# DB4100_DRV_v0_2.net
KiCad netlist of a schematic drawn in Altium Designer
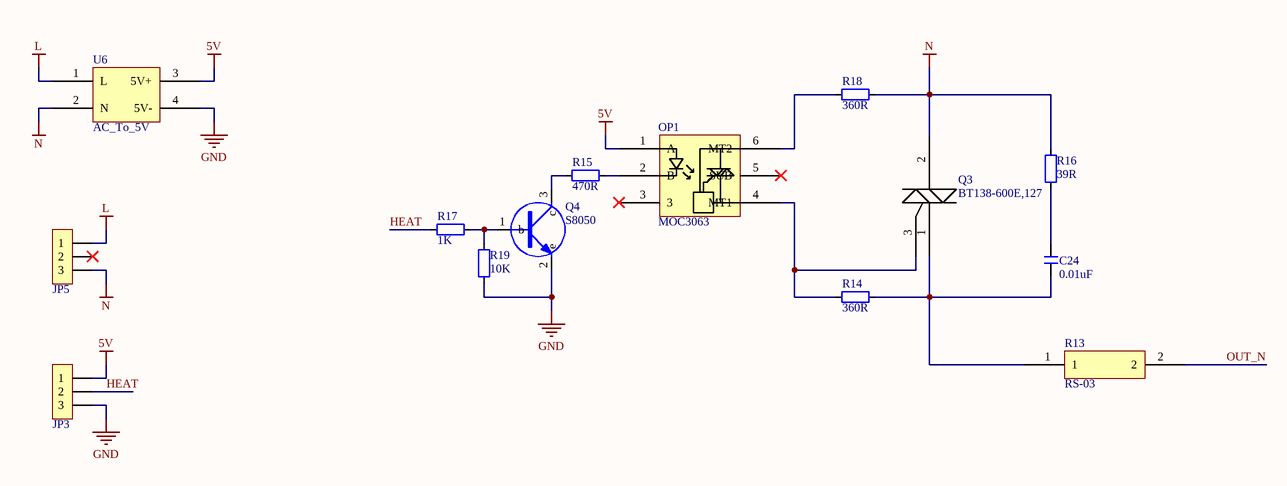
[diagram p0: DB4100_DRV_v0.2.SchDoc]

(export (version "E")
  (design (tool "Eeschema 10.0.6"))
  (components
    (comp (ref "C24")
      (value "0.01uF")
      (footprint "MLCC5.08-A")
      (description "独石电容")
      (fields (field (name "版权归属") "源创客"))
      (libsource (lib "电容") (part "C-MLCC"))
    )
    (comp (ref "JP3")
      (value "HDR-1X3")
      (footprint "XH2.54-3P")
      (description "3P接插件")
      (fields (field (name "版权归属") "源创客"))
      (libsource (lib "排针-排母") (part "Header 3"))
    )
    (comp (ref "JP5")
      (value "HDR-1X3")
      (footprint "VH3.96-3PWB")
      (description "3P接插件")
      (fields (field (name "版权归属") "源创客"))
      (libsource (lib "排针-排母") (part "Header 3"))
    )
    (comp (ref "OP1")
      (value "MOC3063")
      (footprint "MOC3063")
      (description "双向可控硅")
      (libsource (lib "常用芯片") (part "MOC3063"))
    )
    (comp (ref "Q3")
      (value "BT138-600E,127")
      (footprint "BT138-600E,127")
      (description "晶闸管(可控硅)/模块")
      (libsource (lib "二极管-整流桥") (part "BT138-600E,127"))
    )
    (comp (ref "Q4") (value "S8050") (footprint "SOT23-3L") (libsource (lib "三极管") (part "NPN")))
    (comp (ref "R13")
      (value "RS-03")
      (footprint "RS-03")
      (description "电吹风热保护器")
      (libsource (lib "模块器件") (part "RS-03"))
    )
    (comp (ref "R14")
      (value "360R")
      (footprint "R 1206")
      (description "贴片电阻")
      (fields (field (name "版权归属") "源创客"))
      (libsource (lib "") (part "R_1"))
    )
    (comp (ref "R15")
      (value "470R")
      (footprint "R 0603")
      (description "贴片电阻")
      (fields (field (name "版权归属") "源创客"))
      (libsource (lib "电阻") (part "R"))
    )
    (comp (ref "R16")
      (value "39R")
      (footprint "R 1206")
      (description "贴片电阻")
      (fields (field (name "版权归属") "源创客"))
      (libsource (lib "") (part "R_2"))
    )
    (comp (ref "R17")
      (value "1K")
      (footprint "R 0603")
      (description "贴片电阻")
      (fields (field (name "版权归属") "源创客"))
      (libsource (lib "电阻") (part "R"))
    )
    (comp (ref "R18")
      (value "360R")
      (footprint "R 1206")
      (description "贴片电阻")
      (fields (field (name "版权归属") "源创客"))
      (libsource (lib "") (part "R_1"))
    )
    (comp (ref "R19")
      (value "10K")
      (footprint "R 0603")
      (description "贴片电阻")
      (fields (field (name "版权归属") "源创客"))
      (libsource (lib "") (part "R_1"))
    )
    (comp (ref "U6")
      (value "AC_To_5V")
      (footprint "ACTo5v")
      (description "220V转5V降压模块")
      (libsource (lib "变压器") (part "AC_To_5V"))
    )
  )
  (nets
    (net (code "1") (name "/HEAT") (class "Default")
      (node (ref "JP3") (pin "2") (pinfunction "2_2") (pintype "passive"))
      (node (ref "R17") (pin "1") (pinfunction "1_1") (pintype "passive"))
    )
    (net (code "2") (name "/OUT_N") (class "Default")
      (node (ref "R13") (pin "2") (pinfunction "2_2") (pintype "passive"))
    )
    (net (code "3") (name "5V") (class "Default")
      (node (ref "JP3") (pin "1") (pinfunction "1_1") (pintype "passive"))
      (node (ref "OP1") (pin "1") (pinfunction "A_1") (pintype "passive"))
      (node (ref "U6") (pin "3") (pinfunction "5V+_3") (pintype "passive"))
    )
    (net (code "4") (name "GND") (class "Default")
      (node (ref "JP3") (pin "3") (pinfunction "3_3") (pintype "passive"))
      (node (ref "Q4") (pin "2") (pinfunction "e_2") (pintype "passive"))
      (node (ref "R19") (pin "1") (pinfunction "1_1") (pintype "passive"))
      (node (ref "U6") (pin "4") (pinfunction "5V-_4") (pintype "passive"))
    )
    (net (code "5") (name "L") (class "Default")
      (node (ref "JP5") (pin "1") (pinfunction "1_1") (pintype "passive"))
      (node (ref "U6") (pin "1") (pinfunction "L_1") (pintype "passive"))
    )
    (net (code "6") (name "N") (class "Default")
      (node (ref "JP5") (pin "3") (pinfunction "3_3") (pintype "passive"))
      (node (ref "Q3") (pin "2") (pinfunction "2_2") (pintype "passive"))
      (node (ref "R16") (pin "1") (pinfunction "1_1") (pintype "passive"))
      (node (ref "R18") (pin "2") (pinfunction "2_2") (pintype "passive"))
      (node (ref "U6") (pin "2") (pinfunction "N_2") (pintype "passive"))
    )
    (net (code "7") (name "Net-(C24-Pad1)") (class "Default")
      (node (ref "C24") (pin "1") (pinfunction "1_1") (pintype "passive"))
      (node (ref "R16") (pin "2") (pinfunction "2_2") (pintype "passive"))
    )
    (net (code "8") (name "Net-(C24-Pad2)") (class "Default")
      (node (ref "C24") (pin "2") (pinfunction "2_2") (pintype "passive"))
      (node (ref "Q3") (pin "1") (pinfunction "1_1") (pintype "passive"))
      (node (ref "R13") (pin "1") (pinfunction "1_1") (pintype "passive"))
      (node (ref "R14") (pin "2") (pinfunction "2_2") (pintype "passive"))
    )
    (net (code "9") (name "Net-(OP1-B)") (class "Default")
      (node (ref "OP1") (pin "2") (pinfunction "B_2") (pintype "passive"))
      (node (ref "R15") (pin "2") (pinfunction "2_2") (pintype "passive"))
    )
    (net (code "10") (name "Net-(OP1-MT1)") (class "Default")
      (node (ref "OP1") (pin "4") (pinfunction "MT1_4") (pintype "passive"))
      (node (ref "Q3") (pin "3") (pinfunction "3_3") (pintype "passive"))
      (node (ref "R14") (pin "1") (pinfunction "1_1") (pintype "passive"))
    )
    (net (code "11") (name "Net-(OP1-MT2)") (class "Default")
      (node (ref "OP1") (pin "6") (pinfunction "MT2_6") (pintype "passive"))
      (node (ref "R18") (pin "1") (pinfunction "1_1") (pintype "passive"))
    )
    (net (code "12") (name "Net-(Q4-b)") (class "Default")
      (node (ref "Q4") (pin "1") (pinfunction "b_1") (pintype "passive"))
      (node (ref "R17") (pin "2") (pinfunction "2_2") (pintype "passive"))
      (node (ref "R19") (pin "2") (pinfunction "2_2") (pintype "passive"))
    )
    (net (code "13") (name "Net-(Q4-c)") (class "Default")
      (node (ref "Q4") (pin "3") (pinfunction "c_3") (pintype "passive"))
      (node (ref "R15") (pin "1") (pinfunction "1_1") (pintype "passive"))
    )
    (net (code "14") (name "unconnected-(JP5-Pad2)") (class "Default")
      (node (ref "JP5") (pin "2") (pinfunction "2_2") (pintype "passive+no_connect"))
    )
    (net (code "15") (name "unconnected-(OP1-Pad3)") (class "Default")
      (node (ref "OP1") (pin "3") (pinfunction "3_3") (pintype "passive+no_connect"))
    )
    (net (code "16") (name "unconnected-(OP1-SUB-Pad5)") (class "Default")
      (node (ref "OP1") (pin "5") (pinfunction "SUB_5") (pintype "passive+no_connect"))
    )
  )
)
